# ME433_2018.net
KiCad netlist of a schematic drawn in EAGLE
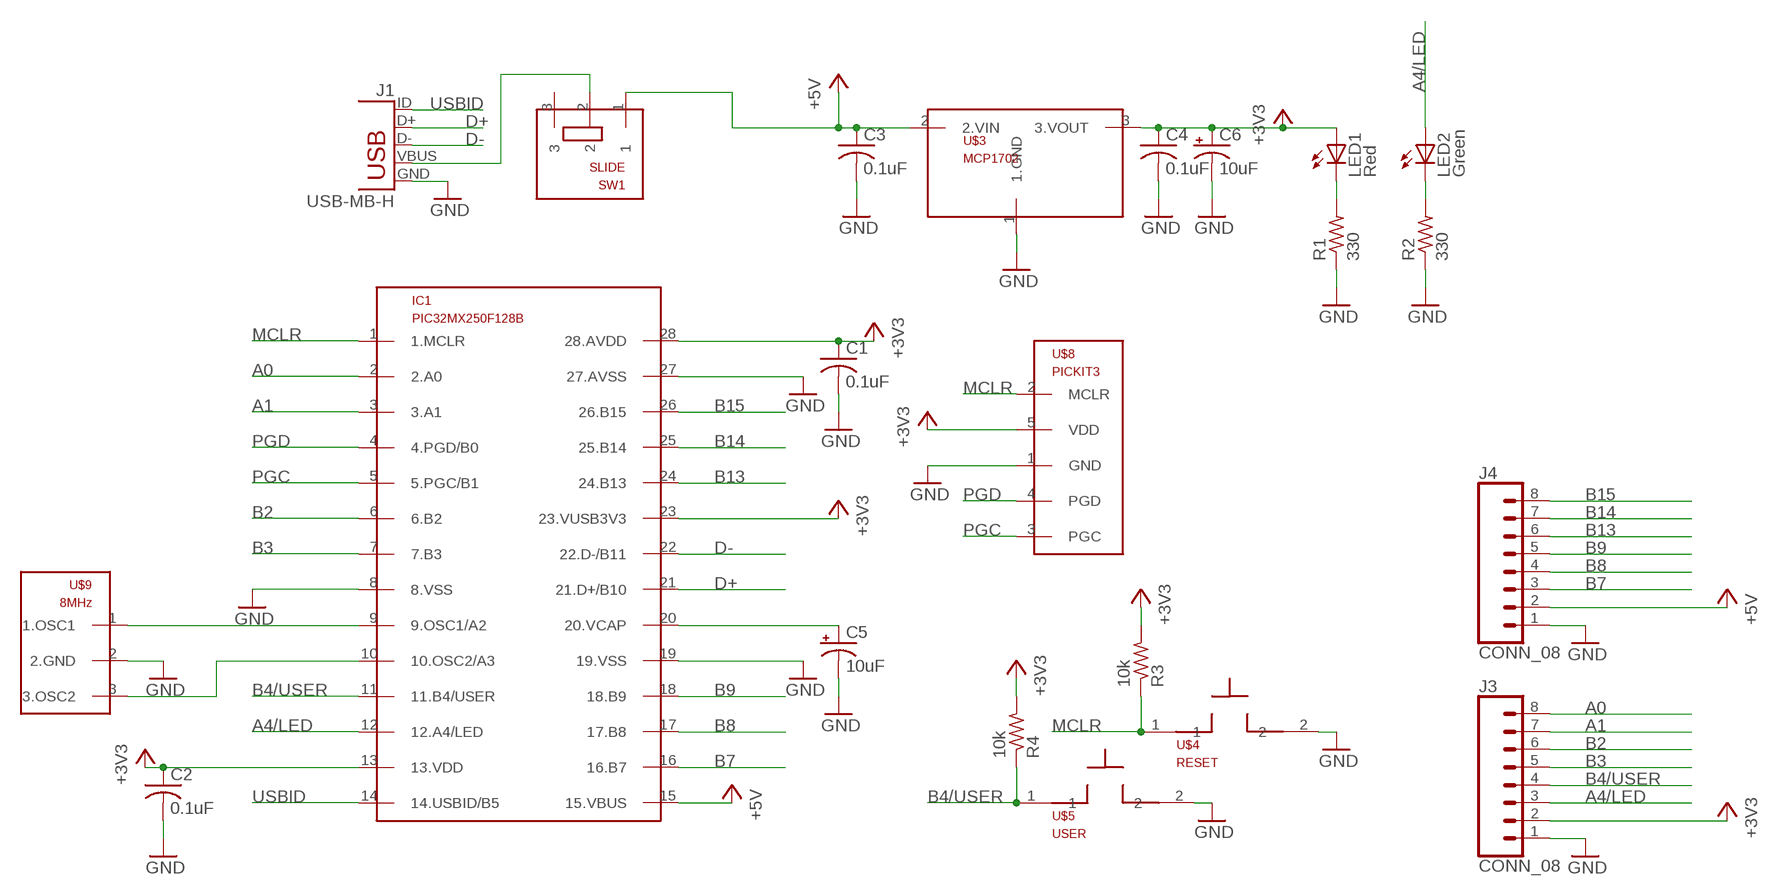
[diagram p0: schematic, sheet 1]

(export (version "E")
  (design (tool "Eeschema 10.0.6"))
  (components
    (comp (ref "C1")
      (value "0.1uF")
      (footprint "eagle-import:C025-025X050")
      (libsource (lib "eagle-import") (part "C-US025-025X050"))
    )
    (comp (ref "C2")
      (value "0.1uF")
      (footprint "eagle-import:C025-025X050")
      (libsource (lib "eagle-import") (part "C-US025-025X050"))
    )
    (comp (ref "C3")
      (value "0.1uF")
      (footprint "eagle-import:C025-025X050")
      (libsource (lib "eagle-import") (part "C-US025-025X050"))
    )
    (comp (ref "C4")
      (value "0.1uF")
      (footprint "eagle-import:C025-025X050")
      (libsource (lib "eagle-import") (part "C-US025-025X050"))
    )
    (comp (ref "C5")
      (value "10uF")
      (footprint "eagle-import:B45181B")
      (libsource (lib "eagle-import") (part "CPOL-USB45181B"))
    )
    (comp (ref "C6")
      (value "10uF")
      (footprint "eagle-import:B45181B")
      (libsource (lib "eagle-import") (part "CPOL-USB45181B"))
    )
    (comp (ref "IC1")
      (value "PIC32MX250F128B")
      (footprint "eagle-import:DIL28-3")
      (libsource (lib "eagle-import") (part "PIC32MX250F128B"))
    )
    (comp (ref "J1")
      (value "USB-MB-H")
      (footprint "eagle-import:USB-MB-H")
      (libsource (lib "eagle-import") (part "USB-MB-H"))
    )
    (comp (ref "J3")
      (value "CONN_08")
      (footprint "eagle-import:1X08")
      (libsource (lib "eagle-import") (part "CONN_08"))
    )
    (comp (ref "J4")
      (value "CONN_08")
      (footprint "eagle-import:1X08")
      (libsource (lib "eagle-import") (part "CONN_08"))
    )
    (comp (ref "LED1")
      (value "Red")
      (footprint "eagle-import:LED3MM")
      (libsource (lib "eagle-import") (part "LED3MM"))
    )
    (comp (ref "LED2")
      (value "Green")
      (footprint "eagle-import:LED3MM")
      (libsource (lib "eagle-import") (part "LED3MM"))
    )
    (comp (ref "R1")
      (value "330")
      (footprint "eagle-import:0207_10")
      (libsource (lib "eagle-import") (part "R-US_0207/10"))
    )
    (comp (ref "R2")
      (value "330")
      (footprint "eagle-import:0207_10")
      (libsource (lib "eagle-import") (part "R-US_0207/10"))
    )
    (comp (ref "R3")
      (value "10k")
      (footprint "eagle-import:0207_10")
      (libsource (lib "eagle-import") (part "R-US_0207/10"))
    )
    (comp (ref "R4")
      (value "10k")
      (footprint "eagle-import:0207_10")
      (libsource (lib "eagle-import") (part "R-US_0207/10"))
    )
    (comp (ref "SW1")
      (value "SLIDE")
      (footprint "eagle-import:SLIDE")
      (libsource (lib "eagle-import") (part "SLIDE"))
    )
    (comp (ref "U$3")
      (value "MCP1702")
      (footprint "eagle-import:TO92")
      (libsource (lib "eagle-import") (part "MCP1702"))
    )
    (comp (ref "U$4")
      (value "RESET")
      (footprint "eagle-import:PB")
      (libsource (lib "eagle-import") (part "PB"))
    )
    (comp (ref "U$5")
      (value "USER")
      (footprint "eagle-import:PB")
      (libsource (lib "eagle-import") (part "PB"))
    )
    (comp (ref "U$8")
      (value "PICKIT3")
      (footprint "eagle-import:1X05")
      (libsource (lib "eagle-import") (part "PICKIT3"))
    )
    (comp (ref "U$9")
      (value "8MHz")
      (footprint "eagle-import:OSC")
      (libsource (lib "eagle-import") (part "OSC"))
    )
  )
  (nets
    (net (code "1") (name "+3V3") (class "Default")
      (node (ref "C1") (pin "1") (pinfunction "1_1") (pintype "passive"))
      (node (ref "C2") (pin "1") (pinfunction "1_1") (pintype "passive"))
      (node (ref "C4") (pin "1") (pinfunction "1_1") (pintype "passive"))
      (node (ref "C6") (pin "+") (pinfunction "+_+") (pintype "passive"))
      (node (ref "IC1") (pin "13") (pinfunction "13.VDD_13") (pintype "bidirectional"))
      (node (ref "IC1") (pin "23") (pinfunction "23.VUSB3V3_23") (pintype "bidirectional"))
      (node (ref "IC1") (pin "28") (pinfunction "28.AVDD_28") (pintype "bidirectional"))
      (node (ref "J3") (pin "2") (pinfunction "2_2") (pintype "passive"))
      (node (ref "LED1") (pin "A") (pinfunction "A_A") (pintype "passive"))
      (node (ref "R3") (pin "2") (pinfunction "2_2") (pintype "passive"))
      (node (ref "R4") (pin "2") (pinfunction "2_2") (pintype "passive"))
      (node (ref "U$3") (pin "3") (pinfunction "3.VOUT_3") (pintype "bidirectional"))
      (node (ref "U$8") (pin "5") (pinfunction "VDD_5") (pintype "bidirectional"))
    )
    (net (code "2") (name "+5V") (class "Default")
      (node (ref "C3") (pin "1") (pinfunction "1_1") (pintype "passive"))
      (node (ref "IC1") (pin "15") (pinfunction "15.VBUS_15") (pintype "bidirectional"))
      (node (ref "J4") (pin "2") (pinfunction "2_2") (pintype "passive"))
      (node (ref "SW1") (pin "1") (pinfunction "1_1") (pintype "bidirectional"))
      (node (ref "U$3") (pin "2") (pinfunction "2.VIN_2") (pintype "bidirectional"))
    )
    (net (code "3") (name "/A0") (class "Default")
      (node (ref "IC1") (pin "2") (pinfunction "2.A0_2") (pintype "bidirectional"))
      (node (ref "J3") (pin "8") (pinfunction "8_8") (pintype "passive"))
    )
    (net (code "4") (name "/A1") (class "Default")
      (node (ref "IC1") (pin "3") (pinfunction "3.A1_3") (pintype "bidirectional"))
      (node (ref "J3") (pin "7") (pinfunction "7_7") (pintype "passive"))
    )
    (net (code "5") (name "/A4{slash}LED") (class "Default")
      (node (ref "IC1") (pin "12") (pinfunction "12.A4/LED_12") (pintype "bidirectional"))
      (node (ref "J3") (pin "3") (pinfunction "3_3") (pintype "passive"))
      (node (ref "LED2") (pin "A") (pinfunction "A_A") (pintype "passive"))
    )
    (net (code "6") (name "/B2") (class "Default")
      (node (ref "IC1") (pin "6") (pinfunction "6.B2_6") (pintype "bidirectional"))
      (node (ref "J3") (pin "6") (pinfunction "6_6") (pintype "passive"))
    )
    (net (code "7") (name "/B3") (class "Default")
      (node (ref "IC1") (pin "7") (pinfunction "7.B3_7") (pintype "bidirectional"))
      (node (ref "J3") (pin "5") (pinfunction "5_5") (pintype "passive"))
    )
    (net (code "8") (name "/B4{slash}USER") (class "Default")
      (node (ref "IC1") (pin "11") (pinfunction "11.B4/USER_11") (pintype "bidirectional"))
      (node (ref "J3") (pin "4") (pinfunction "4_4") (pintype "passive"))
      (node (ref "R4") (pin "1") (pinfunction "1_1") (pintype "passive"))
      (node (ref "U$5") (pin "1") (pinfunction "1_1") (pintype "bidirectional"))
    )
    (net (code "9") (name "/B7") (class "Default")
      (node (ref "IC1") (pin "16") (pinfunction "16.B7_16") (pintype "bidirectional"))
      (node (ref "J4") (pin "3") (pinfunction "3_3") (pintype "passive"))
    )
    (net (code "10") (name "/B8") (class "Default")
      (node (ref "IC1") (pin "17") (pinfunction "17.B8_17") (pintype "bidirectional"))
      (node (ref "J4") (pin "4") (pinfunction "4_4") (pintype "passive"))
    )
    (net (code "11") (name "/B9") (class "Default")
      (node (ref "IC1") (pin "18") (pinfunction "18.B9_18") (pintype "bidirectional"))
      (node (ref "J4") (pin "5") (pinfunction "5_5") (pintype "passive"))
    )
    (net (code "12") (name "/B13") (class "Default")
      (node (ref "IC1") (pin "24") (pinfunction "24.B13_24") (pintype "bidirectional"))
      (node (ref "J4") (pin "6") (pinfunction "6_6") (pintype "passive"))
    )
    (net (code "13") (name "/B14") (class "Default")
      (node (ref "IC1") (pin "25") (pinfunction "25.B14_25") (pintype "bidirectional"))
      (node (ref "J4") (pin "7") (pinfunction "7_7") (pintype "passive"))
    )
    (net (code "14") (name "/B15") (class "Default")
      (node (ref "IC1") (pin "26") (pinfunction "26.B15_26") (pintype "bidirectional"))
      (node (ref "J4") (pin "8") (pinfunction "8_8") (pintype "passive"))
    )
    (net (code "15") (name "/D+") (class "Default")
      (node (ref "IC1") (pin "21") (pinfunction "21.D+/B10_21") (pintype "bidirectional"))
      (node (ref "J1") (pin "D+") (pinfunction "D+_D+") (pintype "bidirectional"))
    )
    (net (code "16") (name "/D-") (class "Default")
      (node (ref "IC1") (pin "22") (pinfunction "22.D-/B11_22") (pintype "bidirectional"))
      (node (ref "J1") (pin "D-") (pinfunction "D-_D-") (pintype "bidirectional"))
    )
    (net (code "17") (name "/MCLR") (class "Default")
      (node (ref "IC1") (pin "1") (pinfunction "1.MCLR_1") (pintype "bidirectional"))
      (node (ref "R3") (pin "1") (pinfunction "1_1") (pintype "passive"))
      (node (ref "U$4") (pin "1") (pinfunction "1_1") (pintype "bidirectional"))
      (node (ref "U$8") (pin "2") (pinfunction "MCLR_2") (pintype "bidirectional"))
    )
    (net (code "18") (name "/PGC") (class "Default")
      (node (ref "IC1") (pin "5") (pinfunction "5.PGC/B1_5") (pintype "bidirectional"))
      (node (ref "U$8") (pin "3") (pinfunction "PGC_3") (pintype "bidirectional"))
    )
    (net (code "19") (name "/PGD") (class "Default")
      (node (ref "IC1") (pin "4") (pinfunction "4.PGD/B0_4") (pintype "bidirectional"))
      (node (ref "U$8") (pin "4") (pinfunction "PGD_4") (pintype "bidirectional"))
    )
    (net (code "20") (name "/USBID") (class "Default")
      (node (ref "IC1") (pin "14") (pinfunction "14.USBID/B5_14") (pintype "bidirectional"))
      (node (ref "J1") (pin "ID") (pinfunction "ID_ID") (pintype "bidirectional"))
    )
    (net (code "21") (name "GND") (class "Default")
      (node (ref "C1") (pin "2") (pinfunction "2_2") (pintype "passive"))
      (node (ref "C2") (pin "2") (pinfunction "2_2") (pintype "passive"))
      (node (ref "C3") (pin "2") (pinfunction "2_2") (pintype "passive"))
      (node (ref "C4") (pin "2") (pinfunction "2_2") (pintype "passive"))
      (node (ref "C5") (pin "-") (pinfunction "-_-") (pintype "passive"))
      (node (ref "C6") (pin "-") (pinfunction "-_-") (pintype "passive"))
      (node (ref "IC1") (pin "19") (pinfunction "19.VSS_19") (pintype "bidirectional"))
      (node (ref "IC1") (pin "27") (pinfunction "27.AVSS_27") (pintype "bidirectional"))
      (node (ref "IC1") (pin "8") (pinfunction "8.VSS_8") (pintype "bidirectional"))
      (node (ref "J1") (pin "GND") (pinfunction "GND_GND") (pintype "bidirectional"))
      (node (ref "J3") (pin "1") (pinfunction "1_1") (pintype "passive"))
      (node (ref "J4") (pin "1") (pinfunction "1_1") (pintype "passive"))
      (node (ref "R1") (pin "1") (pinfunction "1_1") (pintype "passive"))
      (node (ref "R2") (pin "1") (pinfunction "1_1") (pintype "passive"))
      (node (ref "U$3") (pin "1") (pinfunction "1.GND_1") (pintype "bidirectional"))
      (node (ref "U$4") (pin "2") (pinfunction "2_2") (pintype "bidirectional"))
      (node (ref "U$5") (pin "2") (pinfunction "2_2") (pintype "bidirectional"))
      (node (ref "U$8") (pin "1") (pinfunction "GND_1") (pintype "bidirectional"))
      (node (ref "U$9") (pin "2") (pinfunction "2.GND_2") (pintype "bidirectional"))
    )
    (net (code "22") (name "Net-(IC1-9.OSC1{slash}A2)") (class "Default")
      (node (ref "IC1") (pin "9") (pinfunction "9.OSC1/A2_9") (pintype "bidirectional"))
      (node (ref "U$9") (pin "1") (pinfunction "1.OSC1_1") (pintype "bidirectional"))
    )
    (net (code "23") (name "Net-(IC1-10.OSC2{slash}A3)") (class "Default")
      (node (ref "IC1") (pin "10") (pinfunction "10.OSC2/A3_10") (pintype "bidirectional"))
      (node (ref "U$9") (pin "3") (pinfunction "3.OSC2_3") (pintype "bidirectional"))
    )
    (net (code "24") (name "Net-(IC1-20.VCAP)") (class "Default")
      (node (ref "C5") (pin "+") (pinfunction "+_+") (pintype "passive"))
      (node (ref "IC1") (pin "20") (pinfunction "20.VCAP_20") (pintype "bidirectional"))
    )
    (net (code "25") (name "Net-(J1-PadVBUS)") (class "Default")
      (node (ref "J1") (pin "VBUS") (pinfunction "VBUS_VBUS") (pintype "bidirectional"))
      (node (ref "SW1") (pin "2") (pinfunction "2_2") (pintype "bidirectional"))
    )
    (net (code "26") (name "Net-(LED1-C)") (class "Default")
      (node (ref "LED1") (pin "K") (pinfunction "C_K") (pintype "passive"))
      (node (ref "R1") (pin "2") (pinfunction "2_2") (pintype "passive"))
    )
    (net (code "27") (name "Net-(LED2-C)") (class "Default")
      (node (ref "LED2") (pin "K") (pinfunction "C_K") (pintype "passive"))
      (node (ref "R2") (pin "2") (pinfunction "2_2") (pintype "passive"))
    )
    (net (code "28") (name "unconnected-(SW1-Pad3)") (class "Default")
      (node (ref "SW1") (pin "3") (pinfunction "3_3") (pintype "bidirectional"))
    )
  )
)
